# Lamp_Logic_Board_7.net
KiCad netlist of a schematic drawn in EAGLE
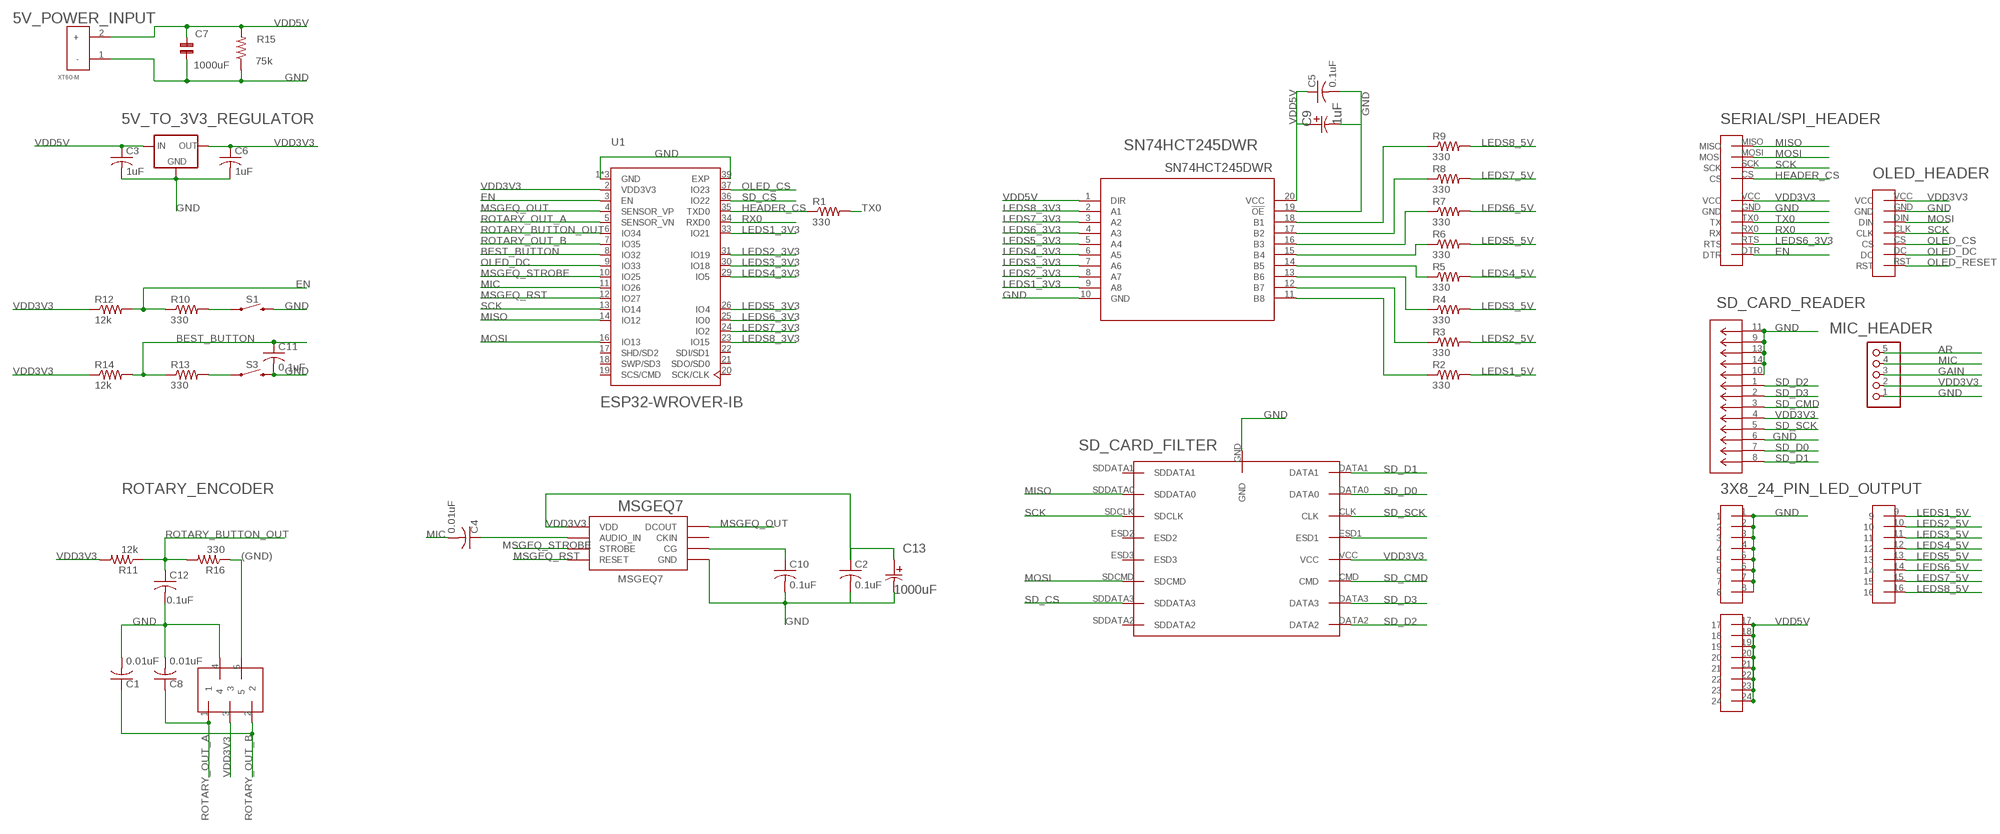
[diagram p0: schematic, sheet 1]

(export (version "E")
  (design (tool "Eeschema 10.0.6"))
  (components
    (comp (ref "3X8_24_PIN_LED_OUTPUT")
      (value "3X8PINHEAD")
      (footprint "eagle-import:3X8PINHEAD")
      (libsource (lib "eagle-import") (part "3X8PINHEAD"))
    )
    (comp (ref "5V_POWER_INPUT")
      (value "XT60-M")
      (footprint "eagle-import:AMASS_XT60-M")
      (fields (field (name "MF") "AMASS"))
      (libsource (lib "eagle-import") (part "XT60-M"))
    )
    (comp (ref "5V_TO_3V3_REGULATOR")
      (value "LM1117MP-1.8")
      (footprint "eagle-import:SOT223")
      (fields (field (name "MF") "Texas Instruments"))
      (libsource (lib "eagle-import") (part "LM1117?-MP1.8"))
    )
    (comp (ref "C1")
      (value "0.01uF")
      (footprint "eagle-import:C0402")
      (libsource (lib "eagle-import") (part "C-USC0402"))
    )
    (comp (ref "C2")
      (value "0.1uF")
      (footprint "eagle-import:C0805")
      (libsource (lib "eagle-import") (part "C-USC0805"))
    )
    (comp (ref "C3")
      (value "1uF")
      (footprint "eagle-import:C0402")
      (libsource (lib "eagle-import") (part "C-USC0402"))
    )
    (comp (ref "C4")
      (value "0.01uF")
      (footprint "eagle-import:C0402")
      (libsource (lib "eagle-import") (part "C-USC0402"))
    )
    (comp (ref "C5")
      (value "0.1uF")
      (footprint "eagle-import:C0805")
      (libsource (lib "eagle-import") (part "C-USC0805"))
    )
    (comp (ref "C6")
      (value "1uF")
      (footprint "eagle-import:C0402")
      (libsource (lib "eagle-import") (part "C-USC0402"))
    )
    (comp (ref "C7")
      (value "1000uF")
      (footprint "eagle-import:ENP2,0-5")
      (libsource (lib "eagle-import") (part "C-BP-2,0X5"))
    )
    (comp (ref "C8")
      (value "0.01uF")
      (footprint "eagle-import:C0402")
      (libsource (lib "eagle-import") (part "C-USC0402"))
    )
    (comp (ref "C9")
      (value "1uF")
      (footprint "eagle-import:CAP_EEFC_B")
      (fields (field (name "MANUFACTURER_PART_NUMBER") "EEEFC1V1R0R"))
      (libsource (lib "eagle-import") (part "EEEFC1V1R0R"))
    )
    (comp (ref "C10")
      (value "0.1uF")
      (footprint "eagle-import:C0805")
      (libsource (lib "eagle-import") (part "C-USC0805"))
    )
    (comp (ref "C11")
      (value "0.1uF")
      (footprint "eagle-import:C0805")
      (libsource (lib "eagle-import") (part "C-USC0805"))
    )
    (comp (ref "C12")
      (value "0.1uF")
      (footprint "eagle-import:C0402")
      (libsource (lib "eagle-import") (part "C-USC0402"))
    )
    (comp (ref "C13")
      (value "1000uF")
      (footprint "eagle-import:CAP_EEFC_B")
      (fields (field (name "MANUFACTURER_PART_NUMBER") "EEEFC1V1R0R"))
      (libsource (lib "eagle-import") (part "EEEFC1V1R0R"))
    )
    (comp (ref "MIC_HEADER")
      (value "PINHD-1X5")
      (footprint "eagle-import:1X05")
      (libsource (lib "eagle-import") (part "PINHD-1X5"))
    )
    (comp (ref "MSGEQ7")
      (value "MSGEQ7DIL")
      (footprint "eagle-import:DIL-08")
      (fields
        (field (name "DIGI-KEY_PART_NUMBER") "1568-1544-ND")
        (field (name "MF") "SparkFun Electronics")
        (field (name "MP") "MSGEQ7")
      )
      (libsource (lib "eagle-import") (part "MSGEQ7DIL"))
    )
    (comp (ref "OLED_HEADER")
      (value "SPIOLED_STANDOFF")
      (footprint "eagle-import:SPIOLED_STADOFF")
      (libsource (lib "eagle-import") (part "SPIOLED_STANDOFF"))
    )
    (comp (ref "R1")
      (value "330")
      (footprint "eagle-import:R1206")
      (libsource (lib "eagle-import") (part "R-US_R1206"))
    )
    (comp (ref "R2")
      (value "330")
      (footprint "eagle-import:R1206")
      (libsource (lib "eagle-import") (part "R-US_R1206"))
    )
    (comp (ref "R3")
      (value "330")
      (footprint "eagle-import:R1206")
      (libsource (lib "eagle-import") (part "R-US_R1206"))
    )
    (comp (ref "R4")
      (value "330")
      (footprint "eagle-import:R1206")
      (libsource (lib "eagle-import") (part "R-US_R1206"))
    )
    (comp (ref "R5")
      (value "330")
      (footprint "eagle-import:R1206")
      (libsource (lib "eagle-import") (part "R-US_R1206"))
    )
    (comp (ref "R6")
      (value "330")
      (footprint "eagle-import:R1206")
      (libsource (lib "eagle-import") (part "R-US_R1206"))
    )
    (comp (ref "R7")
      (value "330")
      (footprint "eagle-import:R1206")
      (libsource (lib "eagle-import") (part "R-US_R1206"))
    )
    (comp (ref "R8")
      (value "330")
      (footprint "eagle-import:R1206")
      (libsource (lib "eagle-import") (part "R-US_R1206"))
    )
    (comp (ref "R9")
      (value "330")
      (footprint "eagle-import:R1206")
      (libsource (lib "eagle-import") (part "R-US_R1206"))
    )
    (comp (ref "R10")
      (value "330")
      (footprint "eagle-import:R1206")
      (libsource (lib "eagle-import") (part "R-US_R1206"))
    )
    (comp (ref "R11")
      (value "12k")
      (footprint "eagle-import:R0603")
      (libsource (lib "eagle-import") (part "R-US_R0603"))
    )
    (comp (ref "R12")
      (value "12k")
      (footprint "eagle-import:R0603")
      (libsource (lib "eagle-import") (part "R-US_R0603"))
    )
    (comp (ref "R13")
      (value "330")
      (footprint "eagle-import:R1206")
      (libsource (lib "eagle-import") (part "R-US_R1206"))
    )
    (comp (ref "R14")
      (value "12k")
      (footprint "eagle-import:R0603")
      (libsource (lib "eagle-import") (part "R-US_R0603"))
    )
    (comp (ref "R15")
      (value "75k")
      (footprint "eagle-import:0309_12")
      (libsource (lib "eagle-import") (part "R-US_0309/12"))
    )
    (comp (ref "R16")
      (value "330")
      (footprint "eagle-import:R1206")
      (libsource (lib "eagle-import") (part "R-US_R1206"))
    )
    (comp (ref "ROTARY_ENCODER")
      (value "EN11-HSM1AF15")
      (footprint "eagle-import:EN11-HSM")
      (libsource (lib "eagle-import") (part "EN11-HSM1AF15"))
    )
    (comp (ref "S1")
      (value "MOMENTARY-SWITCH-SPST-SMD-6.0X3.5MM")
      (footprint "eagle-import:TACTILE_SWITCH_SMD_6.0X3.5MM")
      (libsource (lib "eagle-import") (part "MOMENTARY-SWITCH-SPST-SMD-6.0X3.5MM"))
    )
    (comp (ref "S3")
      (value "MOMENTARY-SWITCH-SPST-SMD-12MM")
      (footprint "eagle-import:TACTILE_SWITCH_SMD_12MM")
      (libsource (lib "eagle-import") (part "MOMENTARY-SWITCH-SPST-SMD-12MM"))
    )
    (comp (ref "SD_CARD_FILTER")
      (value "CM1624-08DE")
      (footprint "eagle-import:CM1624-08DE")
      (libsource (lib "eagle-import") (part "CM1624-08DE"))
    )
    (comp (ref "SD_CARD_READER")
      (value "LLC")
      (footprint "eagle-import:CON00218_8")
      (libsource (lib "eagle-import") (part "LLC"))
    )
    (comp (ref "SERIAL/SPI_HEADER")
      (value "2X6PINHEAD")
      (footprint "eagle-import:2X6PINHEAD")
      (libsource (lib "eagle-import") (part "2X6PINHEAD"))
    )
    (comp (ref "SN74HCT245DWR")
      (value "SN74HCT245DWR")
      (footprint "eagle-import:DW20")
      (libsource (lib "eagle-import") (part "SN74HCT245DWR"))
    )
    (comp (ref "U1")
      (value "ESP32-WROVER-IB")
      (footprint "eagle-import:XCVR_ESP32-WROVER-I")
      (fields (field (name "MF") "Espressif Systems") (field (name "MP") "ESP32-WROVER-I"))
      (libsource (lib "eagle-import") (part "ESP32-WROVER-I"))
    )
  )
  (nets
    (net (code "1") (name "(GND)") (class "Default")
      (node (ref "R16") (pin "1") (pinfunction "1_1") (pintype "passive"))
      (node (ref "ROTARY_ENCODER") (pin "5") (pinfunction "5_5") (pintype "bidirectional"))
    )
    (net (code "2") (name "AR") (class "Default")
      (node (ref "MIC_HEADER") (pin "5") (pinfunction "5_5") (pintype "passive"))
    )
    (net (code "3") (name "BEST_BUTTON") (class "Default")
      (node (ref "C11") (pin "1") (pinfunction "1_1") (pintype "passive"))
      (node (ref "R13") (pin "1") (pinfunction "1_1") (pintype "passive"))
      (node (ref "R14") (pin "2") (pinfunction "2_2") (pintype "passive"))
      (node (ref "U1") (pin "8") (pinfunction "IO32_8") (pintype "bidirectional"))
    )
    (net (code "4") (name "EN") (class "Default")
      (node (ref "R10") (pin "1") (pinfunction "1_1") (pintype "passive"))
      (node (ref "R12") (pin "2") (pinfunction "2_2") (pintype "passive"))
      (node (ref "SERIAL/SPI_HEADER") (pin "DTR") (pinfunction "DTR_DTR") (pintype "bidirectional"))
      (node (ref "U1") (pin "3") (pinfunction "EN_3") (pintype "input"))
    )
    (net (code "5") (name "GAIN") (class "Default")
      (node (ref "MIC_HEADER") (pin "3") (pinfunction "3_3") (pintype "passive"))
    )
    (net (code "6") (name "GND") (class "Default")
      (node (ref "3X8_24_PIN_LED_OUTPUT") (pin "1") (pinfunction "1_1") (pintype "bidirectional"))
      (node (ref "3X8_24_PIN_LED_OUTPUT") (pin "2") (pinfunction "2_2") (pintype "bidirectional"))
      (node (ref "3X8_24_PIN_LED_OUTPUT") (pin "3") (pinfunction "3_3") (pintype "bidirectional"))
      (node (ref "3X8_24_PIN_LED_OUTPUT") (pin "4") (pinfunction "4_4") (pintype "bidirectional"))
      (node (ref "3X8_24_PIN_LED_OUTPUT") (pin "5") (pinfunction "5_5") (pintype "bidirectional"))
      (node (ref "3X8_24_PIN_LED_OUTPUT") (pin "6") (pinfunction "6_6") (pintype "bidirectional"))
      (node (ref "3X8_24_PIN_LED_OUTPUT") (pin "7") (pinfunction "7_7") (pintype "bidirectional"))
      (node (ref "3X8_24_PIN_LED_OUTPUT") (pin "8") (pinfunction "8_8") (pintype "bidirectional"))
      (node (ref "5V_POWER_INPUT") (pin "1") (pinfunction "-_1") (pintype "passive"))
      (node (ref "5V_TO_3V3_REGULATOR") (pin "1") (pinfunction "GND_1") (pintype "input"))
      (node (ref "C1") (pin "2") (pinfunction "2_2") (pintype "passive"))
      (node (ref "C10") (pin "2") (pinfunction "2_2") (pintype "passive"))
      (node (ref "C11") (pin "2") (pinfunction "2_2") (pintype "passive"))
      (node (ref "C12") (pin "2") (pinfunction "2_2") (pintype "passive"))
      (node (ref "C13") (pin "2") (pinfunction "2_2") (pintype "passive"))
      (node (ref "C2") (pin "2") (pinfunction "2_2") (pintype "passive"))
      (node (ref "C3") (pin "2") (pinfunction "2_2") (pintype "passive"))
      (node (ref "C5") (pin "2") (pinfunction "2_2") (pintype "passive"))
      (node (ref "C6") (pin "2") (pinfunction "2_2") (pintype "passive"))
      (node (ref "C7") (pin "1") (pinfunction "1_1") (pintype "passive"))
      (node (ref "C8") (pin "2") (pinfunction "2_2") (pintype "passive"))
      (node (ref "C9") (pin "2") (pinfunction "2_2") (pintype "passive"))
      (node (ref "MIC_HEADER") (pin "1") (pinfunction "1_1") (pintype "passive"))
      (node (ref "MSGEQ7") (pin "2") (pinfunction "GND_2") (pintype "bidirectional"))
      (node (ref "OLED_HEADER") (pin "GND") (pinfunction "GND_GND") (pintype "bidirectional"))
      (node (ref "R15") (pin "1") (pinfunction "1_1") (pintype "passive"))
      (node (ref "ROTARY_ENCODER") (pin "4") (pinfunction "4_4") (pintype "bidirectional"))
      (node (ref "S1") (pin "2") (pinfunction "2_2") (pintype "passive"))
      (node (ref "S3") (pin "3") (pinfunction "2_3") (pintype "passive"))
      (node (ref "SD_CARD_FILTER") (pin "GND") (pinfunction "GND_GND") (pintype "bidirectional"))
      (node (ref "SD_CARD_READER") (pin "10") (pinfunction "10_10") (pintype "passive"))
      (node (ref "SD_CARD_READER") (pin "11") (pinfunction "11_11") (pintype "passive"))
      (node (ref "SD_CARD_READER") (pin "13") (pinfunction "13_13") (pintype "passive"))
      (node (ref "SD_CARD_READER") (pin "14") (pinfunction "14_14") (pintype "passive"))
      (node (ref "SD_CARD_READER") (pin "6") (pinfunction "6_6") (pintype "passive"))
      (node (ref "SD_CARD_READER") (pin "9") (pinfunction "9_9") (pintype "passive"))
      (node (ref "SERIAL/SPI_HEADER") (pin "GND") (pinfunction "GND_GND") (pintype "bidirectional"))
      (node (ref "SN74HCT245DWR") (pin "10") (pinfunction "GND_10") (pintype "power_in"))
      (node (ref "SN74HCT245DWR") (pin "19") (pinfunction "~{OE}_19") (pintype "input"))
      (node (ref "U1") (pin "1") (pinfunction "GND_1") (pintype "power_in"))
      (node (ref "U1") (pin "15") (pinfunction "GND_15") (pintype "power_in"))
      (node (ref "U1") (pin "38") (pinfunction "GND_38") (pintype "power_in"))
      (node (ref "U1") (pin "39") (pinfunction "EXP_39") (pintype "power_in"))
    )
    (net (code "7") (name "HEADER_CS") (class "Default")
      (node (ref "R1") (pin "1") (pinfunction "1_1") (pintype "passive"))
      (node (ref "SERIAL/SPI_HEADER") (pin "CS") (pinfunction "CS_CS") (pintype "bidirectional"))
      (node (ref "U1") (pin "35") (pinfunction "TXD0_35") (pintype "bidirectional"))
    )
    (net (code "8") (name "LEDS1_3V3") (class "Default")
      (node (ref "SN74HCT245DWR") (pin "9") (pinfunction "A8_9") (pintype "bidirectional"))
      (node (ref "U1") (pin "33") (pinfunction "IO21_33") (pintype "bidirectional"))
    )
    (net (code "9") (name "LEDS1_5V") (class "Default")
      (node (ref "3X8_24_PIN_LED_OUTPUT") (pin "9") (pinfunction "9_9") (pintype "bidirectional"))
      (node (ref "R2") (pin "2") (pinfunction "2_2") (pintype "passive"))
    )
    (net (code "10") (name "LEDS2_3V3") (class "Default")
      (node (ref "SN74HCT245DWR") (pin "8") (pinfunction "A7_8") (pintype "bidirectional"))
      (node (ref "U1") (pin "31") (pinfunction "IO19_31") (pintype "bidirectional"))
    )
    (net (code "11") (name "LEDS2_5V") (class "Default")
      (node (ref "3X8_24_PIN_LED_OUTPUT") (pin "10") (pinfunction "10_10") (pintype "bidirectional"))
      (node (ref "R3") (pin "2") (pinfunction "2_2") (pintype "passive"))
    )
    (net (code "12") (name "LEDS3_3V3") (class "Default")
      (node (ref "SN74HCT245DWR") (pin "7") (pinfunction "A6_7") (pintype "bidirectional"))
      (node (ref "U1") (pin "30") (pinfunction "IO18_30") (pintype "bidirectional"))
    )
    (net (code "13") (name "LEDS3_5V") (class "Default")
      (node (ref "3X8_24_PIN_LED_OUTPUT") (pin "11") (pinfunction "11_11") (pintype "bidirectional"))
      (node (ref "R4") (pin "2") (pinfunction "2_2") (pintype "passive"))
    )
    (net (code "14") (name "LEDS4_3V3") (class "Default")
      (node (ref "SN74HCT245DWR") (pin "6") (pinfunction "A5_6") (pintype "bidirectional"))
      (node (ref "U1") (pin "29") (pinfunction "IO5_29") (pintype "bidirectional"))
    )
    (net (code "15") (name "LEDS4_5V") (class "Default")
      (node (ref "3X8_24_PIN_LED_OUTPUT") (pin "12") (pinfunction "12_12") (pintype "bidirectional"))
      (node (ref "R5") (pin "2") (pinfunction "2_2") (pintype "passive"))
    )
    (net (code "16") (name "LEDS5_3V3") (class "Default")
      (node (ref "SN74HCT245DWR") (pin "5") (pinfunction "A4_5") (pintype "bidirectional"))
      (node (ref "U1") (pin "26") (pinfunction "IO4_26") (pintype "bidirectional"))
    )
    (net (code "17") (name "LEDS5_5V") (class "Default")
      (node (ref "3X8_24_PIN_LED_OUTPUT") (pin "13") (pinfunction "13_13") (pintype "bidirectional"))
      (node (ref "R6") (pin "2") (pinfunction "2_2") (pintype "passive"))
    )
    (net (code "18") (name "LEDS6_3V3") (class "Default")
      (node (ref "SERIAL/SPI_HEADER") (pin "RTS") (pinfunction "RTS_RTS") (pintype "bidirectional"))
      (node (ref "SN74HCT245DWR") (pin "4") (pinfunction "A3_4") (pintype "bidirectional"))
      (node (ref "U1") (pin "25") (pinfunction "IO0_25") (pintype "bidirectional"))
    )
    (net (code "19") (name "LEDS6_5V") (class "Default")
      (node (ref "3X8_24_PIN_LED_OUTPUT") (pin "14") (pinfunction "14_14") (pintype "bidirectional"))
      (node (ref "R7") (pin "2") (pinfunction "2_2") (pintype "passive"))
    )
    (net (code "20") (name "LEDS7_3V3") (class "Default")
      (node (ref "SN74HCT245DWR") (pin "3") (pinfunction "A2_3") (pintype "bidirectional"))
      (node (ref "U1") (pin "24") (pinfunction "IO2_24") (pintype "bidirectional"))
    )
    (net (code "21") (name "LEDS7_5V") (class "Default")
      (node (ref "3X8_24_PIN_LED_OUTPUT") (pin "15") (pinfunction "15_15") (pintype "bidirectional"))
      (node (ref "R8") (pin "2") (pinfunction "2_2") (pintype "passive"))
    )
    (net (code "22") (name "LEDS8_3V3") (class "Default")
      (node (ref "SN74HCT245DWR") (pin "2") (pinfunction "A1_2") (pintype "bidirectional"))
      (node (ref "U1") (pin "23") (pinfunction "IO15_23") (pintype "bidirectional"))
    )
    (net (code "23") (name "LEDS8_5V") (class "Default")
      (node (ref "3X8_24_PIN_LED_OUTPUT") (pin "16") (pinfunction "16_16") (pintype "bidirectional"))
      (node (ref "R9") (pin "2") (pinfunction "2_2") (pintype "passive"))
    )
    (net (code "24") (name "MIC") (class "Default")
      (node (ref "C4") (pin "2") (pinfunction "2_2") (pintype "passive"))
      (node (ref "MIC_HEADER") (pin "4") (pinfunction "4_4") (pintype "passive"))
      (node (ref "U1") (pin "11") (pinfunction "IO26_11") (pintype "bidirectional"))
    )
    (net (code "25") (name "MISO") (class "Default")
      (node (ref "SD_CARD_FILTER") (pin "SDDATA0") (pinfunction "SDDATA0_SDDATA0") (pintype "bidirectional"))
      (node (ref "SERIAL/SPI_HEADER") (pin "MISO") (pinfunction "MISO_MISO") (pintype "bidirectional"))
      (node (ref "U1") (pin "14") (pinfunction "IO12_14") (pintype "bidirectional"))
    )
    (net (code "26") (name "MOSI") (class "Default")
      (node (ref "OLED_HEADER") (pin "DIN") (pinfunction "DIN_DIN") (pintype "bidirectional"))
      (node (ref "SD_CARD_FILTER") (pin "SDCMD") (pinfunction "SDCMD_SDCMD") (pintype "bidirectional"))
      (node (ref "SERIAL/SPI_HEADER") (pin "MOSI") (pinfunction "MOSI_MOSI") (pintype "bidirectional"))
      (node (ref "U1") (pin "16") (pinfunction "IO13_16") (pintype "bidirectional"))
    )
    (net (code "27") (name "MSGEQ_OUT") (class "Default")
      (node (ref "MSGEQ7") (pin "3") (pinfunction "DCOUT_3") (pintype "bidirectional"))
      (node (ref "U1") (pin "4") (pinfunction "SENSOR_VP_4") (pintype "input"))
    )
    (net (code "28") (name "MSGEQ_RST") (class "Default")
      (node (ref "MSGEQ7") (pin "7") (pinfunction "RESET_7") (pintype "input"))
      (node (ref "U1") (pin "12") (pinfunction "IO27_12") (pintype "bidirectional"))
    )
    (net (code "29") (name "MSGEQ_STROBE") (class "Default")
      (node (ref "MSGEQ7") (pin "4") (pinfunction "STROBE_4") (pintype "input"))
      (node (ref "U1") (pin "10") (pinfunction "IO25_10") (pintype "bidirectional"))
    )
    (net (code "30") (name "Net-(MSGEQ7-AUDIO_IN)") (class "Default")
      (node (ref "C4") (pin "1") (pinfunction "1_1") (pintype "passive"))
      (node (ref "MSGEQ7") (pin "5") (pinfunction "AUDIO_IN_5") (pintype "input"))
    )
    (net (code "31") (name "Net-(MSGEQ7-CG)") (class "Default")
      (node (ref "C10") (pin "1") (pinfunction "1_1") (pintype "passive"))
      (node (ref "MSGEQ7") (pin "6") (pinfunction "CG_6") (pintype "bidirectional"))
    )
    (net (code "32") (name "Net-(R10-Pad2)") (class "Default")
      (node (ref "R10") (pin "2") (pinfunction "2_2") (pintype "passive"))
      (node (ref "S1") (pin "1") (pinfunction "1_1") (pintype "passive"))
    )
    (net (code "33") (name "Net-(R13-Pad2)") (class "Default")
      (node (ref "R13") (pin "2") (pinfunction "2_2") (pintype "passive"))
      (node (ref "S3") (pin "1") (pinfunction "1_1") (pintype "passive"))
    )
    (net (code "34") (name "Net-(SN74HCT245DWR-B1)") (class "Default")
      (node (ref "R9") (pin "1") (pinfunction "1_1") (pintype "passive"))
      (node (ref "SN74HCT245DWR") (pin "18") (pinfunction "B1_18") (pintype "bidirectional"))
    )
    (net (code "35") (name "Net-(SN74HCT245DWR-B2)") (class "Default")
      (node (ref "R8") (pin "1") (pinfunction "1_1") (pintype "passive"))
      (node (ref "SN74HCT245DWR") (pin "17") (pinfunction "B2_17") (pintype "bidirectional"))
    )
    (net (code "36") (name "Net-(SN74HCT245DWR-B3)") (class "Default")
      (node (ref "R7") (pin "1") (pinfunction "1_1") (pintype "passive"))
      (node (ref "SN74HCT245DWR") (pin "16") (pinfunction "B3_16") (pintype "bidirectional"))
    )
    (net (code "37") (name "Net-(SN74HCT245DWR-B4)") (class "Default")
      (node (ref "R6") (pin "1") (pinfunction "1_1") (pintype "passive"))
      (node (ref "SN74HCT245DWR") (pin "15") (pinfunction "B4_15") (pintype "bidirectional"))
    )
    (net (code "38") (name "Net-(SN74HCT245DWR-B5)") (class "Default")
      (node (ref "R5") (pin "1") (pinfunction "1_1") (pintype "passive"))
      (node (ref "SN74HCT245DWR") (pin "14") (pinfunction "B5_14") (pintype "bidirectional"))
    )
    (net (code "39") (name "Net-(SN74HCT245DWR-B6)") (class "Default")
      (node (ref "R4") (pin "1") (pinfunction "1_1") (pintype "passive"))
      (node (ref "SN74HCT245DWR") (pin "13") (pinfunction "B6_13") (pintype "bidirectional"))
    )
    (net (code "40") (name "Net-(SN74HCT245DWR-B7)") (class "Default")
      (node (ref "R3") (pin "1") (pinfunction "1_1") (pintype "passive"))
      (node (ref "SN74HCT245DWR") (pin "12") (pinfunction "B7_12") (pintype "bidirectional"))
    )
    (net (code "41") (name "Net-(SN74HCT245DWR-B8)") (class "Default")
      (node (ref "R2") (pin "1") (pinfunction "1_1") (pintype "passive"))
      (node (ref "SN74HCT245DWR") (pin "11") (pinfunction "B8_11") (pintype "bidirectional"))
    )
    (net (code "42") (name "OLED_CS") (class "Default")
      (node (ref "OLED_HEADER") (pin "CS") (pinfunction "CS_CS") (pintype "bidirectional"))
      (node (ref "U1") (pin "37") (pinfunction "IO23_37") (pintype "bidirectional"))
    )
    (net (code "43") (name "OLED_DC") (class "Default")
      (node (ref "OLED_HEADER") (pin "DC") (pinfunction "DC_DC") (pintype "bidirectional"))
      (node (ref "U1") (pin "9") (pinfunction "IO33_9") (pintype "bidirectional"))
    )
    (net (code "44") (name "OLED_RESET") (class "Default")
      (node (ref "OLED_HEADER") (pin "RST") (pinfunction "RST_RST") (pintype "bidirectional"))
    )
    (net (code "45") (name "ROTARY_BUTTON_OUT") (class "Default")
      (node (ref "C12") (pin "1") (pinfunction "1_1") (pintype "passive"))
      (node (ref "R11") (pin "1") (pinfunction "1_1") (pintype "passive"))
      (node (ref "R16") (pin "2") (pinfunction "2_2") (pintype "passive"))
      (node (ref "U1") (pin "6") (pinfunction "IO34_6") (pintype "input"))
    )
    (net (code "46") (name "ROTARY_OUT_A") (class "Default")
      (node (ref "C8") (pin "1") (pinfunction "1_1") (pintype "passive"))
      (node (ref "ROTARY_ENCODER") (pin "1") (pinfunction "1_1") (pintype "passive"))
      (node (ref "U1") (pin "5") (pinfunction "SENSOR_VN_5") (pintype "input"))
    )
    (net (code "47") (name "ROTARY_OUT_B") (class "Default")
      (node (ref "C1") (pin "1") (pinfunction "1_1") (pintype "passive"))
      (node (ref "ROTARY_ENCODER") (pin "2") (pinfunction "2_2") (pintype "passive"))
      (node (ref "U1") (pin "7") (pinfunction "IO35_7") (pintype "input"))
    )
    (net (code "48") (name "RX0") (class "Default")
      (node (ref "SERIAL/SPI_HEADER") (pin "RX0") (pinfunction "RX_RX0") (pintype "bidirectional"))
      (node (ref "U1") (pin "34") (pinfunction "RXD0_34") (pintype "bidirectional"))
    )
    (net (code "49") (name "SCK") (class "Default")
      (node (ref "OLED_HEADER") (pin "CLK") (pinfunction "CLK_CLK") (pintype "bidirectional"))
      (node (ref "SD_CARD_FILTER") (pin "SDCLK") (pinfunction "SDCLK_SDCLK") (pintype "bidirectional"))
      (node (ref "SERIAL/SPI_HEADER") (pin "SCK") (pinfunction "SCK_SCK") (pintype "bidirectional"))
      (node (ref "U1") (pin "13") (pinfunction "IO14_13") (pintype "bidirectional"))
    )
    (net (code "50") (name "SD_CMD") (class "Default")
      (node (ref "SD_CARD_FILTER") (pin "CMD") (pinfunction "CMD_CMD") (pintype "bidirectional"))
      (node (ref "SD_CARD_READER") (pin "3") (pinfunction "3_3") (pintype "passive"))
    )
    (net (code "51") (name "SD_CS") (class "Default")
      (node (ref "SD_CARD_FILTER") (pin "SDDATA3") (pinfunction "SDDATA3_SDDATA3") (pintype "bidirectional"))
      (node (ref "U1") (pin "36") (pinfunction "IO22_36") (pintype "bidirectional"))
    )
    (net (code "52") (name "SD_D0") (class "Default")
      (node (ref "SD_CARD_FILTER") (pin "DATA0") (pinfunction "DATA0_DATA0") (pintype "bidirectional"))
      (node (ref "SD_CARD_READER") (pin "7") (pinfunction "7_7") (pintype "passive"))
    )
    (net (code "53") (name "SD_D1") (class "Default")
      (node (ref "SD_CARD_FILTER") (pin "DATA1") (pinfunction "DATA1_DATA1") (pintype "bidirectional"))
      (node (ref "SD_CARD_READER") (pin "8") (pinfunction "8_8") (pintype "passive"))
    )
    (net (code "54") (name "SD_D2") (class "Default")
      (node (ref "SD_CARD_FILTER") (pin "DATA2") (pinfunction "DATA2_DATA2") (pintype "bidirectional"))
      (node (ref "SD_CARD_READER") (pin "1") (pinfunction "1_1") (pintype "passive"))
    )
    (net (code "55") (name "SD_D3") (class "Default")
      (node (ref "SD_CARD_FILTER") (pin "DATA3") (pinfunction "DATA3_DATA3") (pintype "bidirectional"))
      (node (ref "SD_CARD_READER") (pin "2") (pinfunction "2_2") (pintype "passive"))
    )
    (net (code "56") (name "SD_SCK") (class "Default")
      (node (ref "SD_CARD_FILTER") (pin "CLK") (pinfunction "CLK_CLK") (pintype "bidirectional"))
      (node (ref "SD_CARD_READER") (pin "5") (pinfunction "5_5") (pintype "passive"))
    )
    (net (code "57") (name "TX0") (class "Default")
      (node (ref "R1") (pin "2") (pinfunction "2_2") (pintype "passive"))
      (node (ref "SERIAL/SPI_HEADER") (pin "TX0") (pinfunction "TX_TX0") (pintype "bidirectional"))
    )
    (net (code "58") (name "VDD3V3") (class "Default")
      (node (ref "5V_TO_3V3_REGULATOR") (pin "2") (pinfunction "OUT_2") (pintype "passive"))
      (node (ref "5V_TO_3V3_REGULATOR") (pin "4") (pinfunction "OUT_4") (pintype "passive"))
      (node (ref "C13") (pin "1") (pinfunction "1_1") (pintype "passive"))
      (node (ref "C2") (pin "1") (pinfunction "1_1") (pintype "passive"))
      (node (ref "C6") (pin "1") (pinfunction "1_1") (pintype "passive"))
      (node (ref "MIC_HEADER") (pin "2") (pinfunction "2_2") (pintype "passive"))
      (node (ref "MSGEQ7") (pin "1") (pinfunction "VDD_1") (pintype "input"))
      (node (ref "OLED_HEADER") (pin "VCC") (pinfunction "VCC_VCC") (pintype "bidirectional"))
      (node (ref "R11") (pin "2") (pinfunction "2_2") (pintype "passive"))
      (node (ref "R12") (pin "1") (pinfunction "1_1") (pintype "passive"))
      (node (ref "R14") (pin "1") (pinfunction "1_1") (pintype "passive"))
      (node (ref "ROTARY_ENCODER") (pin "3") (pinfunction "3_3") (pintype "passive"))
      (node (ref "SD_CARD_FILTER") (pin "VCC") (pinfunction "VCC_VCC") (pintype "bidirectional"))
      (node (ref "SD_CARD_READER") (pin "4") (pinfunction "4_4") (pintype "passive"))
      (node (ref "SERIAL/SPI_HEADER") (pin "VCC") (pinfunction "VCC_VCC") (pintype "bidirectional"))
      (node (ref "U1") (pin "2") (pinfunction "VDD3V3_2") (pintype "power_in"))
    )
    (net (code "59") (name "VDD5V") (class "Default")
      (node (ref "3X8_24_PIN_LED_OUTPUT") (pin "17") (pinfunction "17_17") (pintype "bidirectional"))
      (node (ref "3X8_24_PIN_LED_OUTPUT") (pin "18") (pinfunction "18_18") (pintype "bidirectional"))
      (node (ref "3X8_24_PIN_LED_OUTPUT") (pin "19") (pinfunction "19_19") (pintype "bidirectional"))
      (node (ref "3X8_24_PIN_LED_OUTPUT") (pin "20") (pinfunction "20_20") (pintype "bidirectional"))
      (node (ref "3X8_24_PIN_LED_OUTPUT") (pin "21") (pinfunction "21_21") (pintype "bidirectional"))
      (node (ref "3X8_24_PIN_LED_OUTPUT") (pin "22") (pinfunction "22_22") (pintype "bidirectional"))
      (node (ref "3X8_24_PIN_LED_OUTPUT") (pin "23") (pinfunction "23_23") (pintype "bidirectional"))
      (node (ref "3X8_24_PIN_LED_OUTPUT") (pin "24") (pinfunction "24_24") (pintype "bidirectional"))
      (node (ref "5V_POWER_INPUT") (pin "2") (pinfunction "+_2") (pintype "passive"))
      (node (ref "5V_TO_3V3_REGULATOR") (pin "3") (pinfunction "IN_3") (pintype "input"))
      (node (ref "C3") (pin "1") (pinfunction "1_1") (pintype "passive"))
      (node (ref "C5") (pin "1") (pinfunction "1_1") (pintype "passive"))
      (node (ref "C7") (pin "2") (pinfunction "2_2") (pintype "passive"))
      (node (ref "C9") (pin "1") (pinfunction "1_1") (pintype "passive"))
      (node (ref "R15") (pin "2") (pinfunction "2_2") (pintype "passive"))
      (node (ref "SN74HCT245DWR") (pin "1") (pinfunction "DIR_1") (pintype "input"))
      (node (ref "SN74HCT245DWR") (pin "20") (pinfunction "VCC_20") (pintype "power_in"))
    )
    (net (code "60") (name "unconnected-(MSGEQ7-CKIN-Pad8)") (class "Default")
      (node (ref "MSGEQ7") (pin "8") (pinfunction "CKIN_8") (pintype "bidirectional"))
    )
    (net (code "61") (name "unconnected-(SD_CARD_FILTER-PadESD1)") (class "Default")
      (node (ref "SD_CARD_FILTER") (pin "ESD1") (pinfunction "ESD1_ESD1") (pintype "bidirectional"))
    )
    (net (code "62") (name "unconnected-(SD_CARD_FILTER-PadESD2)") (class "Default")
      (node (ref "SD_CARD_FILTER") (pin "ESD2") (pinfunction "ESD2_ESD2") (pintype "bidirectional"))
    )
    (net (code "63") (name "unconnected-(SD_CARD_FILTER-PadESD3)") (class "Default")
      (node (ref "SD_CARD_FILTER") (pin "ESD3") (pinfunction "ESD3_ESD3") (pintype "bidirectional"))
    )
    (net (code "64") (name "unconnected-(SD_CARD_FILTER-PadSDDATA1)") (class "Default")
      (node (ref "SD_CARD_FILTER") (pin "SDDATA1") (pinfunction "SDDATA1_SDDATA1") (pintype "bidirectional"))
    )
    (net (code "65") (name "unconnected-(SD_CARD_FILTER-PadSDDATA2)") (class "Default")
      (node (ref "SD_CARD_FILTER") (pin "SDDATA2") (pinfunction "SDDATA2_SDDATA2") (pintype "bidirectional"))
    )
    (net (code "66") (name "unconnected-(U1-SCK{slash}CLK-Pad20)") (class "Default")
      (node (ref "U1") (pin "20") (pinfunction "SCK/CLK_20") (pintype "bidirectional"))
    )
    (net (code "67") (name "unconnected-(U1-SCS{slash}CMD-Pad19)") (class "Default")
      (node (ref "U1") (pin "19") (pinfunction "SCS/CMD_19") (pintype "bidirectional"))
    )
    (net (code "68") (name "unconnected-(U1-SDI{slash}SD1-Pad22)") (class "Default")
      (node (ref "U1") (pin "22") (pinfunction "SDI/SD1_22") (pintype "bidirectional"))
    )
    (net (code "69") (name "unconnected-(U1-SDO{slash}SD0-Pad21)") (class "Default")
      (node (ref "U1") (pin "21") (pinfunction "SDO/SD0_21") (pintype "bidirectional"))
    )
    (net (code "70") (name "unconnected-(U1-SHD{slash}SD2-Pad17)") (class "Default")
      (node (ref "U1") (pin "17") (pinfunction "SHD/SD2_17") (pintype "bidirectional"))
    )
    (net (code "71") (name "unconnected-(U1-SWP{slash}SD3-Pad18)") (class "Default")
      (node (ref "U1") (pin "18") (pinfunction "SWP/SD3_18") (pintype "bidirectional"))
    )
  )
)
